# Slave3_flying_pcb_v1.net
KiCad netlist of a schematic drawn in Altium Designer
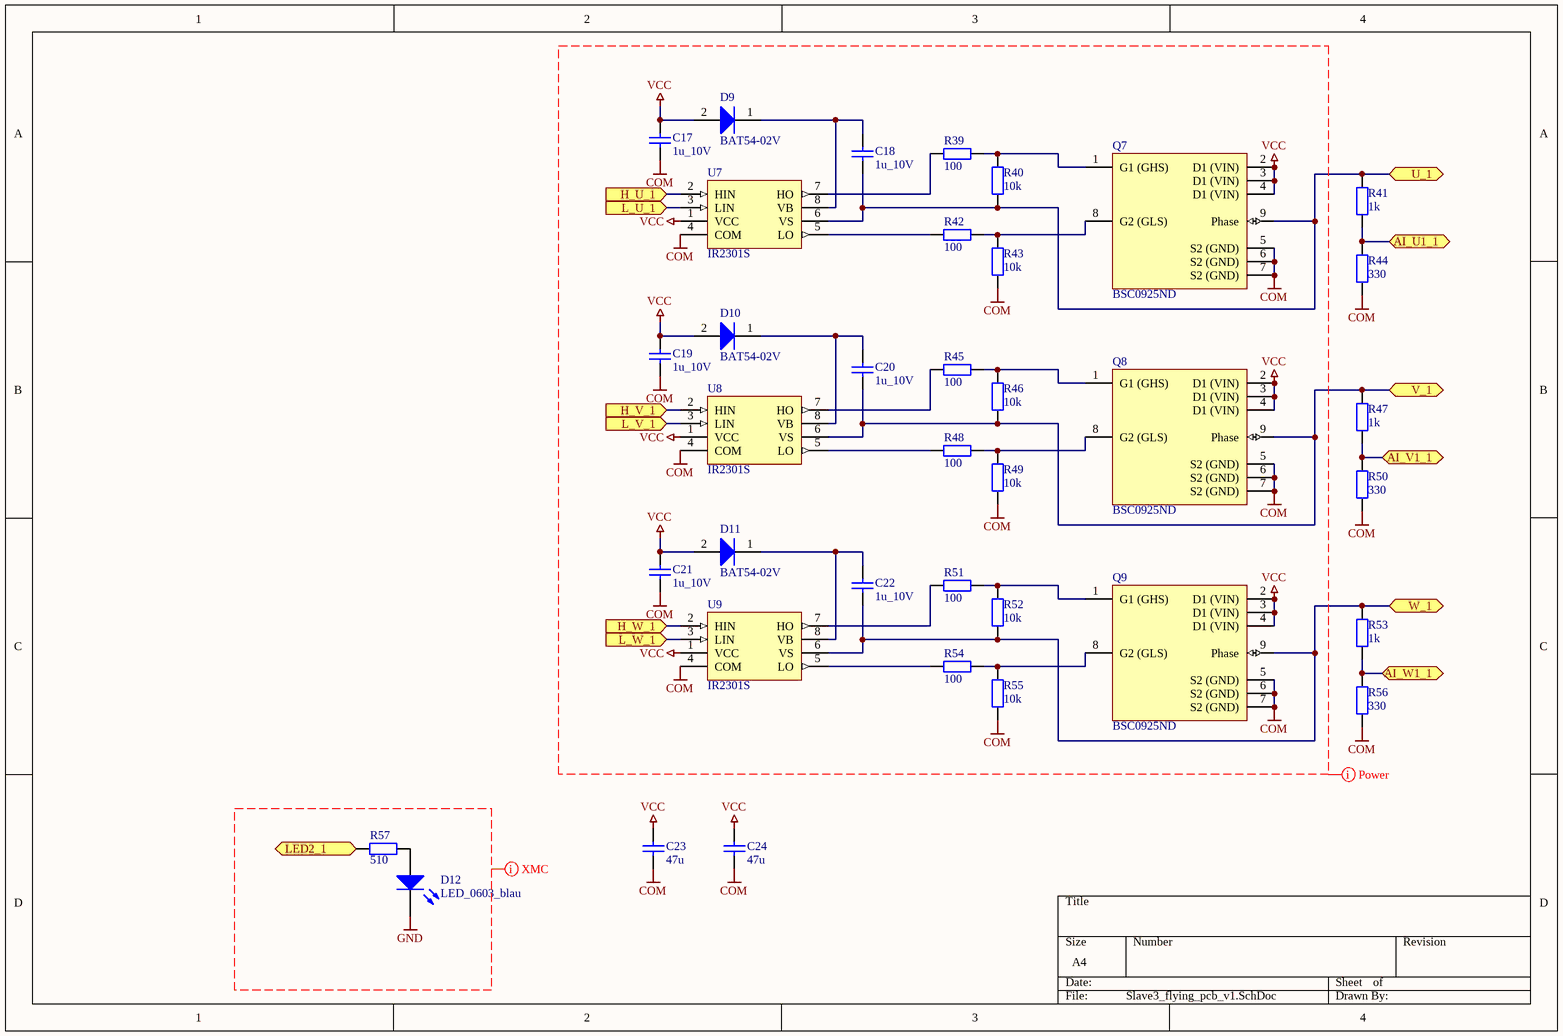
[diagram p0: Slave3_flying_pcb_v1.SchDoc]

(export (version "E")
  (design (tool "Eeschema 10.0.6"))
  (components
    (comp (ref "C17")
      (value "1u_10V")
      (footprint "1608[0603]")
      (fields (field (name "VOLTAGE") "10V"))
      (libsource (lib "Capacitors$") (part "Cap_133"))
    )
    (comp (ref "C18")
      (value "1u_10V")
      (footprint "1608[0603]")
      (fields (field (name "VOLTAGE") "10V"))
      (libsource (lib "Capacitors$") (part "Cap_133"))
    )
    (comp (ref "C19")
      (value "1u_10V")
      (footprint "1608[0603]")
      (fields (field (name "VOLTAGE") "10V"))
      (libsource (lib "Capacitors$") (part "Cap_133"))
    )
    (comp (ref "C20")
      (value "1u_10V")
      (footprint "1608[0603]")
      (fields (field (name "VOLTAGE") "10V"))
      (libsource (lib "Capacitors$") (part "Cap_133"))
    )
    (comp (ref "C21")
      (value "1u_10V")
      (footprint "1608[0603]")
      (fields (field (name "VOLTAGE") "10V"))
      (libsource (lib "Capacitors$") (part "Cap_133"))
    )
    (comp (ref "C22")
      (value "1u_10V")
      (footprint "1608[0603]")
      (fields (field (name "VOLTAGE") "10V"))
      (libsource (lib "Capacitors$") (part "Cap_133"))
    )
    (comp (ref "C23")
      (value "47u")
      (footprint "_0805")
      (fields (field (name "VOLTAGE") "50V"))
      (libsource (lib "Capacitors$") (part "Cap_133"))
    )
    (comp (ref "C24")
      (value "47u")
      (footprint "_0805")
      (fields (field (name "VOLTAGE") "50V"))
      (libsource (lib "Capacitors$") (part "Cap_133"))
    )
    (comp (ref "D9")
      (value "BAT54-02V")
      (footprint "INF-SC79_V")
      (description "Silicon Schottky Diode, SC79, Reel, Green")
      (fields (field (name "MANUFACTURER") "Infineon"))
      (libsource (lib "Pinus_V2") (part "BAT54-02V"))
    )
    (comp (ref "D10")
      (value "BAT54-02V")
      (footprint "INF-SC79_V")
      (description "Silicon Schottky Diode, SC79, Reel, Green")
      (fields (field (name "MANUFACTURER") "Infineon"))
      (libsource (lib "Pinus_V2") (part "BAT54-02V"))
    )
    (comp (ref "D11")
      (value "BAT54-02V")
      (footprint "INF-SC79_V")
      (description "Silicon Schottky Diode, SC79, Reel, Green")
      (fields (field (name "MANUFACTURER") "Infineon"))
      (libsource (lib "Pinus_V2") (part "BAT54-02V"))
    )
    (comp (ref "D12")
      (value "LED_0603_blau")
      (footprint "LED_0603")
      (libsource (lib "flying_pcb_v1") (part "DIODE_60"))
    )
    (comp (ref "Q7")
      (value "BSC0925ND")
      (footprint "INF-PG-TISON-8_V")
      (description "N-Channel OptiMOS Power-MOSFET, 30 V VDS, 40 A ID, -55 to 150 degC, PG-TISON-8, Reel, Green")
      (fields (field (name "MANUFACTURER") "Infineon"))
      (libsource (lib "Pinus_V2") (part "BSC0925ND"))
    )
    (comp (ref "Q8")
      (value "BSC0925ND")
      (footprint "INF-PG-TISON-8_V")
      (description "N-Channel OptiMOS Power-MOSFET, 30 V VDS, 40 A ID, -55 to 150 degC, PG-TISON-8, Reel, Green")
      (fields (field (name "MANUFACTURER") "Infineon"))
      (libsource (lib "Pinus_V2") (part "BSC0925ND"))
    )
    (comp (ref "Q9")
      (value "BSC0925ND")
      (footprint "INF-PG-TISON-8_V")
      (description "N-Channel OptiMOS Power-MOSFET, 30 V VDS, 40 A ID, -55 to 150 degC, PG-TISON-8, Reel, Green")
      (fields (field (name "MANUFACTURER") "Infineon"))
      (libsource (lib "Pinus_V2") (part "BSC0925ND"))
    )
    (comp (ref "R39")
      (value "100")
      (footprint "1608[0603]")
      (fields (field (name "Comment") "Res_0603"))
      (libsource (lib "") (part "Res_6_1"))
    )
    (comp (ref "R40")
      (value "10k")
      (footprint "1608[0603]")
      (fields (field (name "Comment") "Res_0603"))
      (libsource (lib "Resistors$") (part "Res_6"))
    )
    (comp (ref "R41")
      (value "1k")
      (footprint "1608[0603]")
      (fields (field (name "Comment") "Res_0603"))
      (libsource (lib "Resistors$") (part "Res_6"))
    )
    (comp (ref "R42")
      (value "100")
      (footprint "1608[0603]")
      (fields (field (name "Comment") "Res_0603"))
      (libsource (lib "") (part "Res_6_1"))
    )
    (comp (ref "R43")
      (value "10k")
      (footprint "1608[0603]")
      (fields (field (name "Comment") "Res_0603"))
      (libsource (lib "Resistors$") (part "Res_6"))
    )
    (comp (ref "R44")
      (value "330")
      (footprint "1608[0603]")
      (fields (field (name "Comment") "Res_0603"))
      (libsource (lib "Resistors$") (part "Res_6"))
    )
    (comp (ref "R45")
      (value "100")
      (footprint "1608[0603]")
      (fields (field (name "Comment") "Res_0603"))
      (libsource (lib "") (part "Res_6_1"))
    )
    (comp (ref "R46")
      (value "10k")
      (footprint "1608[0603]")
      (fields (field (name "Comment") "Res_0603"))
      (libsource (lib "Resistors$") (part "Res_6"))
    )
    (comp (ref "R47")
      (value "1k")
      (footprint "1608[0603]")
      (fields (field (name "Comment") "Res_0603"))
      (libsource (lib "Resistors$") (part "Res_6"))
    )
    (comp (ref "R48")
      (value "100")
      (footprint "1608[0603]")
      (fields (field (name "Comment") "Res_0603"))
      (libsource (lib "") (part "Res_6_1"))
    )
    (comp (ref "R49")
      (value "10k")
      (footprint "1608[0603]")
      (fields (field (name "Comment") "Res_0603"))
      (libsource (lib "Resistors$") (part "Res_6"))
    )
    (comp (ref "R50")
      (value "330")
      (footprint "1608[0603]")
      (fields (field (name "Comment") "Res_0603"))
      (libsource (lib "Resistors$") (part "Res_6"))
    )
    (comp (ref "R51")
      (value "100")
      (footprint "1608[0603]")
      (fields (field (name "Comment") "Res_0603"))
      (libsource (lib "") (part "Res_6_1"))
    )
    (comp (ref "R52")
      (value "10k")
      (footprint "1608[0603]")
      (fields (field (name "Comment") "Res_0603"))
      (libsource (lib "Resistors$") (part "Res_6"))
    )
    (comp (ref "R53")
      (value "1k")
      (footprint "1608[0603]")
      (fields (field (name "Comment") "Res_0603"))
      (libsource (lib "Resistors$") (part "Res_6"))
    )
    (comp (ref "R54")
      (value "100")
      (footprint "1608[0603]")
      (fields (field (name "Comment") "Res_0603"))
      (libsource (lib "") (part "Res_6_1"))
    )
    (comp (ref "R55")
      (value "10k")
      (footprint "1608[0603]")
      (fields (field (name "Comment") "Res_0603"))
      (libsource (lib "Resistors$") (part "Res_6"))
    )
    (comp (ref "R56")
      (value "330")
      (footprint "1608[0603]")
      (fields (field (name "Comment") "Res_0603"))
      (libsource (lib "Resistors$") (part "Res_6"))
    )
    (comp (ref "R57")
      (value "510")
      (footprint "1608[0603]")
      (fields (field (name "Comment") "Res_0603"))
      (libsource (lib "") (part "Res_6_2"))
    )
    (comp (ref "U7")
      (value "IR2301S")
      (footprint "SO-8_N")
      (description "High and Low Side Driver")
      (fields (field (name "PUBLISHER") "Altium Limited"))
      (libsource (lib "Pinus_V2") (part "IR2101S"))
    )
    (comp (ref "U8")
      (value "IR2301S")
      (footprint "SO-8_N")
      (description "High and Low Side Driver")
      (fields (field (name "PUBLISHER") "Altium Limited"))
      (libsource (lib "Pinus_V2") (part "IR2101S"))
    )
    (comp (ref "U9")
      (value "IR2301S")
      (footprint "SO-8_N")
      (description "High and Low Side Driver")
      (fields (field (name "PUBLISHER") "Altium Limited"))
      (libsource (lib "Pinus_V2") (part "IR2101S"))
    )
  )
  (nets
    (net (code "1") (name "/AI_U1_1") (class "Default")
      (node (ref "R41") (pin "2") (pinfunction "2_2") (pintype "passive"))
      (node (ref "R44") (pin "1") (pinfunction "1_1") (pintype "passive"))
    )
    (net (code "2") (name "/AI_V1_1") (class "Default")
      (node (ref "R47") (pin "2") (pinfunction "2_2") (pintype "passive"))
      (node (ref "R50") (pin "1") (pinfunction "1_1") (pintype "passive"))
    )
    (net (code "3") (name "/AI_W1_1") (class "Default")
      (node (ref "R53") (pin "2") (pinfunction "2_2") (pintype "passive"))
      (node (ref "R56") (pin "1") (pinfunction "1_1") (pintype "passive"))
    )
    (net (code "4") (name "/H_U_1") (class "Default")
      (node (ref "U7") (pin "2") (pinfunction "HIN_2") (pintype "input"))
    )
    (net (code "5") (name "/H_V_1") (class "Default")
      (node (ref "U8") (pin "2") (pinfunction "HIN_2") (pintype "input"))
    )
    (net (code "6") (name "/H_W_1") (class "Default")
      (node (ref "U9") (pin "2") (pinfunction "HIN_2") (pintype "input"))
    )
    (net (code "7") (name "/LED2_1") (class "Default")
      (node (ref "R57") (pin "1") (pinfunction "1_1") (pintype "passive"))
    )
    (net (code "8") (name "/L_U_1") (class "Default")
      (node (ref "U7") (pin "3") (pinfunction "LIN_3") (pintype "input"))
    )
    (net (code "9") (name "/L_V_1") (class "Default")
      (node (ref "U8") (pin "3") (pinfunction "LIN_3") (pintype "input"))
    )
    (net (code "10") (name "/L_W_1") (class "Default")
      (node (ref "U9") (pin "3") (pinfunction "LIN_3") (pintype "input"))
    )
    (net (code "11") (name "/U_1") (class "Default")
      (node (ref "C18") (pin "2") (pinfunction "2_2") (pintype "passive"))
      (node (ref "Q7") (pin "9") (pinfunction "Phase_9") (pintype "bidirectional"))
      (node (ref "R40") (pin "2") (pinfunction "2_2") (pintype "passive"))
      (node (ref "R41") (pin "1") (pinfunction "1_1") (pintype "passive"))
      (node (ref "U7") (pin "6") (pinfunction "VS_6") (pintype "power_in"))
    )
    (net (code "12") (name "/V_1") (class "Default")
      (node (ref "C20") (pin "2") (pinfunction "2_2") (pintype "passive"))
      (node (ref "Q8") (pin "9") (pinfunction "Phase_9") (pintype "bidirectional"))
      (node (ref "R46") (pin "2") (pinfunction "2_2") (pintype "passive"))
      (node (ref "R47") (pin "1") (pinfunction "1_1") (pintype "passive"))
      (node (ref "U8") (pin "6") (pinfunction "VS_6") (pintype "power_in"))
    )
    (net (code "13") (name "/W_1") (class "Default")
      (node (ref "C22") (pin "2") (pinfunction "2_2") (pintype "passive"))
      (node (ref "Q9") (pin "9") (pinfunction "Phase_9") (pintype "bidirectional"))
      (node (ref "R52") (pin "2") (pinfunction "2_2") (pintype "passive"))
      (node (ref "R53") (pin "1") (pinfunction "1_1") (pintype "passive"))
      (node (ref "U9") (pin "6") (pinfunction "VS_6") (pintype "power_in"))
    )
    (net (code "14") (name "COM") (class "Default")
      (node (ref "C17") (pin "2") (pinfunction "2_2") (pintype "passive"))
      (node (ref "C19") (pin "2") (pinfunction "2_2") (pintype "passive"))
      (node (ref "C21") (pin "2") (pinfunction "2_2") (pintype "passive"))
      (node (ref "C23") (pin "1") (pinfunction "1_1") (pintype "passive"))
      (node (ref "C24") (pin "1") (pinfunction "1_1") (pintype "passive"))
      (node (ref "Q7") (pin "5") (pinfunction "S2_(GND)_5") (pintype "passive"))
      (node (ref "Q7") (pin "6") (pinfunction "S2_(GND)_6") (pintype "passive"))
      (node (ref "Q7") (pin "7") (pinfunction "S2_(GND)_7") (pintype "passive"))
      (node (ref "Q8") (pin "5") (pinfunction "S2_(GND)_5") (pintype "passive"))
      (node (ref "Q8") (pin "6") (pinfunction "S2_(GND)_6") (pintype "passive"))
      (node (ref "Q8") (pin "7") (pinfunction "S2_(GND)_7") (pintype "passive"))
      (node (ref "Q9") (pin "5") (pinfunction "S2_(GND)_5") (pintype "passive"))
      (node (ref "Q9") (pin "6") (pinfunction "S2_(GND)_6") (pintype "passive"))
      (node (ref "Q9") (pin "7") (pinfunction "S2_(GND)_7") (pintype "passive"))
      (node (ref "R43") (pin "2") (pinfunction "2_2") (pintype "passive"))
      (node (ref "R44") (pin "2") (pinfunction "2_2") (pintype "passive"))
      (node (ref "R49") (pin "2") (pinfunction "2_2") (pintype "passive"))
      (node (ref "R50") (pin "2") (pinfunction "2_2") (pintype "passive"))
      (node (ref "R55") (pin "2") (pinfunction "2_2") (pintype "passive"))
      (node (ref "R56") (pin "2") (pinfunction "2_2") (pintype "passive"))
      (node (ref "U7") (pin "4") (pinfunction "COM_4") (pintype "power_in"))
      (node (ref "U8") (pin "4") (pinfunction "COM_4") (pintype "power_in"))
      (node (ref "U9") (pin "4") (pinfunction "COM_4") (pintype "power_in"))
    )
    (net (code "15") (name "GND") (class "Default")
      (node (ref "D12") (pin "2") (pinfunction "2_2") (pintype "passive"))
    )
    (net (code "16") (name "Net-(D9-K)") (class "Default")
      (node (ref "C18") (pin "1") (pinfunction "1_1") (pintype "passive"))
      (node (ref "D9") (pin "1") (pinfunction "K_1") (pintype "passive"))
      (node (ref "U7") (pin "8") (pinfunction "VB_8") (pintype "power_in"))
    )
    (net (code "17") (name "Net-(D10-K)") (class "Default")
      (node (ref "C20") (pin "1") (pinfunction "1_1") (pintype "passive"))
      (node (ref "D10") (pin "1") (pinfunction "K_1") (pintype "passive"))
      (node (ref "U8") (pin "8") (pinfunction "VB_8") (pintype "power_in"))
    )
    (net (code "18") (name "Net-(D11-K)") (class "Default")
      (node (ref "C22") (pin "1") (pinfunction "1_1") (pintype "passive"))
      (node (ref "D11") (pin "1") (pinfunction "K_1") (pintype "passive"))
      (node (ref "U9") (pin "8") (pinfunction "VB_8") (pintype "power_in"))
    )
    (net (code "19") (name "Net-(D12-Pad1)") (class "Default")
      (node (ref "D12") (pin "1") (pinfunction "1_1") (pintype "passive"))
      (node (ref "R57") (pin "2") (pinfunction "2_2") (pintype "passive"))
    )
    (net (code "20") (name "Net-(Q7-G1_(GHS))") (class "Default")
      (node (ref "Q7") (pin "1") (pinfunction "G1_(GHS)_1") (pintype "passive"))
      (node (ref "R39") (pin "1") (pinfunction "1_1") (pintype "passive"))
      (node (ref "R40") (pin "1") (pinfunction "1_1") (pintype "passive"))
    )
    (net (code "21") (name "Net-(Q7-G2_(GLS))") (class "Default")
      (node (ref "Q7") (pin "8") (pinfunction "G2_(GLS)_8") (pintype "passive"))
      (node (ref "R42") (pin "1") (pinfunction "1_1") (pintype "passive"))
      (node (ref "R43") (pin "1") (pinfunction "1_1") (pintype "passive"))
    )
    (net (code "22") (name "Net-(Q8-G1_(GHS))") (class "Default")
      (node (ref "Q8") (pin "1") (pinfunction "G1_(GHS)_1") (pintype "passive"))
      (node (ref "R45") (pin "1") (pinfunction "1_1") (pintype "passive"))
      (node (ref "R46") (pin "1") (pinfunction "1_1") (pintype "passive"))
    )
    (net (code "23") (name "Net-(Q8-G2_(GLS))") (class "Default")
      (node (ref "Q8") (pin "8") (pinfunction "G2_(GLS)_8") (pintype "passive"))
      (node (ref "R48") (pin "1") (pinfunction "1_1") (pintype "passive"))
      (node (ref "R49") (pin "1") (pinfunction "1_1") (pintype "passive"))
    )
    (net (code "24") (name "Net-(Q9-G1_(GHS))") (class "Default")
      (node (ref "Q9") (pin "1") (pinfunction "G1_(GHS)_1") (pintype "passive"))
      (node (ref "R51") (pin "1") (pinfunction "1_1") (pintype "passive"))
      (node (ref "R52") (pin "1") (pinfunction "1_1") (pintype "passive"))
    )
    (net (code "25") (name "Net-(Q9-G2_(GLS))") (class "Default")
      (node (ref "Q9") (pin "8") (pinfunction "G2_(GLS)_8") (pintype "passive"))
      (node (ref "R54") (pin "1") (pinfunction "1_1") (pintype "passive"))
      (node (ref "R55") (pin "1") (pinfunction "1_1") (pintype "passive"))
    )
    (net (code "26") (name "Net-(U7-HO)") (class "Default")
      (node (ref "R39") (pin "2") (pinfunction "2_2") (pintype "passive"))
      (node (ref "U7") (pin "7") (pinfunction "HO_7") (pintype "output"))
    )
    (net (code "27") (name "Net-(U7-LO)") (class "Default")
      (node (ref "R42") (pin "2") (pinfunction "2_2") (pintype "passive"))
      (node (ref "U7") (pin "5") (pinfunction "LO_5") (pintype "output"))
    )
    (net (code "28") (name "Net-(U8-HO)") (class "Default")
      (node (ref "R45") (pin "2") (pinfunction "2_2") (pintype "passive"))
      (node (ref "U8") (pin "7") (pinfunction "HO_7") (pintype "output"))
    )
    (net (code "29") (name "Net-(U8-LO)") (class "Default")
      (node (ref "R48") (pin "2") (pinfunction "2_2") (pintype "passive"))
      (node (ref "U8") (pin "5") (pinfunction "LO_5") (pintype "output"))
    )
    (net (code "30") (name "Net-(U9-HO)") (class "Default")
      (node (ref "R51") (pin "2") (pinfunction "2_2") (pintype "passive"))
      (node (ref "U9") (pin "7") (pinfunction "HO_7") (pintype "output"))
    )
    (net (code "31") (name "Net-(U9-LO)") (class "Default")
      (node (ref "R54") (pin "2") (pinfunction "2_2") (pintype "passive"))
      (node (ref "U9") (pin "5") (pinfunction "LO_5") (pintype "output"))
    )
    (net (code "32") (name "VCC") (class "Default")
      (node (ref "C17") (pin "1") (pinfunction "1_1") (pintype "passive"))
      (node (ref "C19") (pin "1") (pinfunction "1_1") (pintype "passive"))
      (node (ref "C21") (pin "1") (pinfunction "1_1") (pintype "passive"))
      (node (ref "C23") (pin "2") (pinfunction "2_2") (pintype "passive"))
      (node (ref "C24") (pin "2") (pinfunction "2_2") (pintype "passive"))
      (node (ref "D10") (pin "2") (pinfunction "A_2") (pintype "passive"))
      (node (ref "D11") (pin "2") (pinfunction "A_2") (pintype "passive"))
      (node (ref "D9") (pin "2") (pinfunction "A_2") (pintype "passive"))
      (node (ref "Q7") (pin "2") (pinfunction "D1_(VIN)_2") (pintype "passive"))
      (node (ref "Q7") (pin "3") (pinfunction "D1_(VIN)_3") (pintype "passive"))
      (node (ref "Q7") (pin "4") (pinfunction "D1_(VIN)_4") (pintype "passive"))
      (node (ref "Q8") (pin "2") (pinfunction "D1_(VIN)_2") (pintype "passive"))
      (node (ref "Q8") (pin "3") (pinfunction "D1_(VIN)_3") (pintype "passive"))
      (node (ref "Q8") (pin "4") (pinfunction "D1_(VIN)_4") (pintype "passive"))
      (node (ref "Q9") (pin "2") (pinfunction "D1_(VIN)_2") (pintype "passive"))
      (node (ref "Q9") (pin "3") (pinfunction "D1_(VIN)_3") (pintype "passive"))
      (node (ref "Q9") (pin "4") (pinfunction "D1_(VIN)_4") (pintype "passive"))
      (node (ref "U7") (pin "1") (pinfunction "VCC_1") (pintype "power_in"))
      (node (ref "U8") (pin "1") (pinfunction "VCC_1") (pintype "power_in"))
      (node (ref "U9") (pin "1") (pinfunction "VCC_1") (pintype "power_in"))
    )
  )
)
